# E3-LED_v2.net
KiCad netlist of a schematic drawn in EAGLE
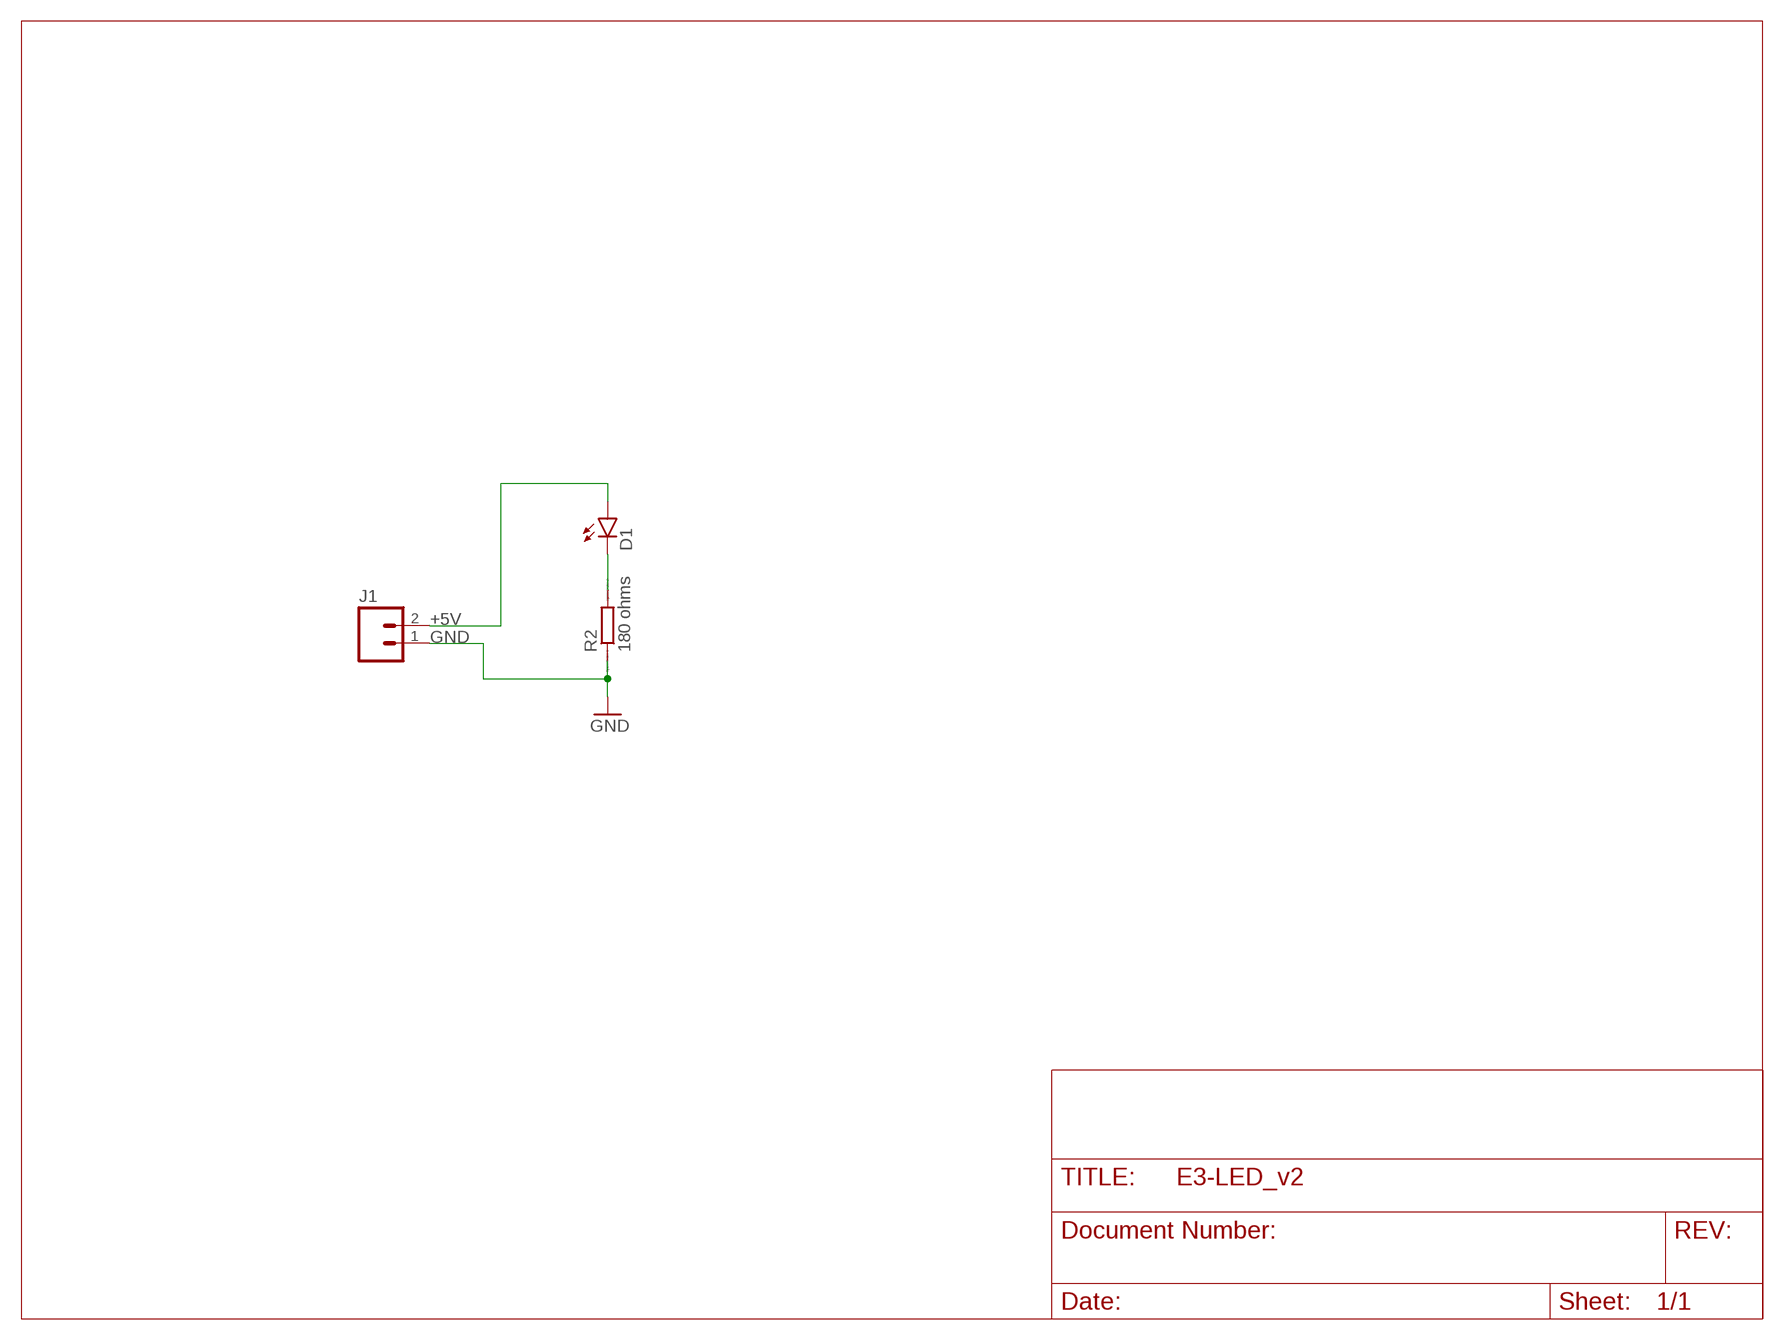
[diagram p0: schematic, sheet 1]

(export (version "E")
  (design (tool "Eeschema 10.0.6"))
  (components
    (comp (ref "D1")
      (value "LED5MM")
      (footprint "eagle-import:LED5MM")
      (libsource (lib "eagle-import") (part "LED5MM"))
    )
    (comp (ref "J1")
      (value "M02PTH")
      (footprint "eagle-import:1X02")
      (libsource (lib "eagle-import") (part "M02PTH"))
    )
    (comp (ref "R2")
      (value "180 ohms")
      (footprint "eagle-import:R0603")
      (libsource (lib "eagle-import") (part "RR0603"))
    )
  )
  (nets
    (net (code "1") (name "/+5V") (class "Default")
      (node (ref "D1") (pin "A") (pinfunction "A_A") (pintype "passive"))
      (node (ref "J1") (pin "2") (pinfunction "2_2") (pintype "passive"))
    )
    (net (code "2") (name "GND") (class "Default")
      (node (ref "J1") (pin "1") (pinfunction "1_1") (pintype "passive"))
      (node (ref "R2") (pin "1") (pinfunction "1_1") (pintype "passive"))
    )
    (net (code "3") (name "Net-(D1-C)") (class "Default")
      (node (ref "D1") (pin "K") (pinfunction "C_K") (pintype "passive"))
      (node (ref "R2") (pin "2") (pinfunction "2_2") (pintype "passive"))
    )
  )
)
